# PCB_RIGID_USBC_MALE.net
KiCad netlist of a schematic drawn in EAGLE
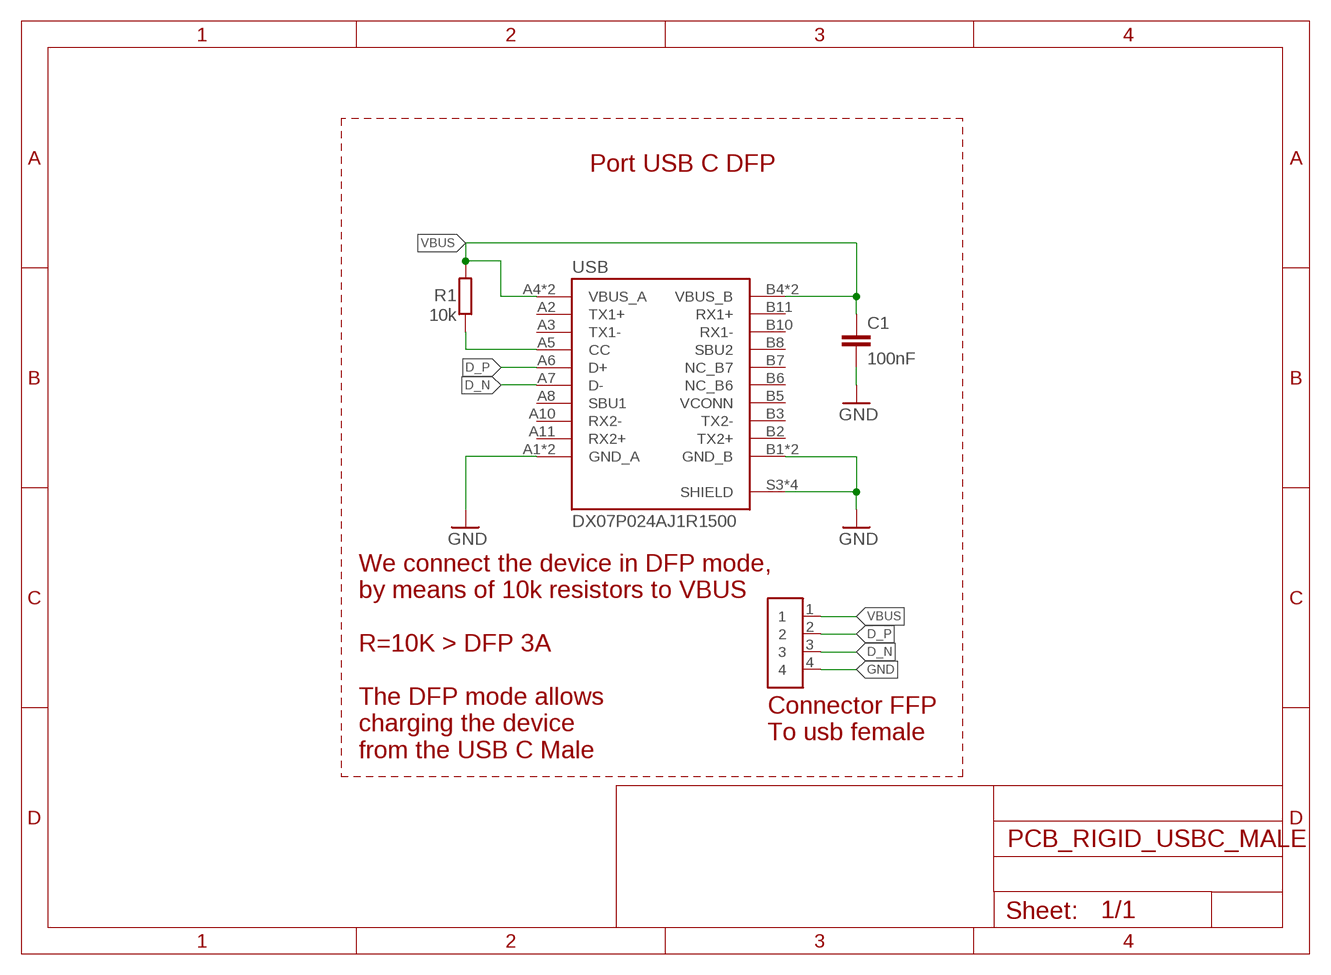
[diagram p0: schematic, sheet 1]

(export (version "E")
  (design (tool "Eeschema 10.0.6"))
  (components
    (comp (ref "C1")
      (value "100nF")
      (footprint "eagle-import:C0603")
      (libsource (lib "eagle-import") (part "C_0603"))
    )
    (comp (ref "FFP")
      (value "CONN_FLEX_2.5MM")
      (footprint "eagle-import:CONN_FLEX_2.5MM")
      (libsource (lib "eagle-import") (part "CONN_FLEX_2.5MM"))
    )
    (comp (ref "R1")
      (value "10k")
      (footprint "eagle-import:R0603")
      (libsource (lib "eagle-import") (part "R_0603"))
    )
    (comp (ref "USB")
      (value "DX07P024AJ1R1500")
      (footprint "eagle-import:JAE_DX07P024AJ1R1500")
      (fields (field (name "MF") "JAE Electronics"))
      (libsource (lib "eagle-import") (part "DX07P024AJ1R1500"))
    )
  )
  (nets
    (net (code "1") (name "D_N") (class "Default")
      (node (ref "FFP") (pin "3") (pinfunction "3_3") (pintype "bidirectional"))
      (node (ref "USB") (pin "A7") (pinfunction "D-_A7") (pintype "bidirectional"))
    )
    (net (code "2") (name "D_P") (class "Default")
      (node (ref "FFP") (pin "2") (pinfunction "2_2") (pintype "bidirectional"))
      (node (ref "USB") (pin "A6") (pinfunction "D+_A6") (pintype "bidirectional"))
    )
    (net (code "3") (name "GND") (class "Default")
      (node (ref "C1") (pin "2") (pinfunction "2_2") (pintype "passive"))
      (node (ref "FFP") (pin "4") (pinfunction "4_4") (pintype "bidirectional"))
      (node (ref "USB") (pin "A1") (pinfunction "GND_A_A1") (pintype "power_in"))
      (node (ref "USB") (pin "A12") (pinfunction "GND_A_A12") (pintype "power_in"))
      (node (ref "USB") (pin "B1") (pinfunction "GND_B_B1") (pintype "power_in"))
      (node (ref "USB") (pin "B12") (pinfunction "GND_B_B12") (pintype "power_in"))
      (node (ref "USB") (pin "S3") (pinfunction "SHIELD_S3") (pintype "passive"))
      (node (ref "USB") (pin "S4") (pinfunction "SHIELD_S4") (pintype "passive"))
      (node (ref "USB") (pin "S5") (pinfunction "SHIELD_S5") (pintype "passive"))
      (node (ref "USB") (pin "S6") (pinfunction "SHIELD_S6") (pintype "passive"))
    )
    (net (code "4") (name "Net-(USB-CC)") (class "Default")
      (node (ref "R1") (pin "1") (pinfunction "1_1") (pintype "passive"))
      (node (ref "USB") (pin "A5") (pinfunction "CC_A5") (pintype "bidirectional"))
    )
    (net (code "5") (name "VBUS") (class "Default")
      (node (ref "C1") (pin "1") (pinfunction "1_1") (pintype "passive"))
      (node (ref "FFP") (pin "1") (pinfunction "1_1") (pintype "bidirectional"))
      (node (ref "R1") (pin "2") (pinfunction "2_2") (pintype "passive"))
      (node (ref "USB") (pin "A4") (pinfunction "VBUS_A_A4") (pintype "power_in"))
      (node (ref "USB") (pin "A9") (pinfunction "VBUS_A_A9") (pintype "power_in"))
      (node (ref "USB") (pin "B4") (pinfunction "VBUS_B_B4") (pintype "power_in"))
      (node (ref "USB") (pin "B9") (pinfunction "VBUS_B_B9") (pintype "power_in"))
    )
    (net (code "6") (name "unconnected-(USB-NC_B6-PadB6)") (class "Default")
      (node (ref "USB") (pin "B6") (pinfunction "NC_B6_B6") (pintype "no_connect"))
    )
    (net (code "7") (name "unconnected-(USB-NC_B7-PadB7)") (class "Default")
      (node (ref "USB") (pin "B7") (pinfunction "NC_B7_B7") (pintype "no_connect"))
    )
    (net (code "8") (name "unconnected-(USB-RX1+-PadB11)") (class "Default")
      (node (ref "USB") (pin "B11") (pinfunction "RX1+_B11") (pintype "bidirectional"))
    )
    (net (code "9") (name "unconnected-(USB-RX1--PadB10)") (class "Default")
      (node (ref "USB") (pin "B10") (pinfunction "RX1-_B10") (pintype "bidirectional"))
    )
    (net (code "10") (name "unconnected-(USB-RX2+-PadA11)") (class "Default")
      (node (ref "USB") (pin "A11") (pinfunction "RX2+_A11") (pintype "bidirectional"))
    )
    (net (code "11") (name "unconnected-(USB-RX2--PadA10)") (class "Default")
      (node (ref "USB") (pin "A10") (pinfunction "RX2-_A10") (pintype "bidirectional"))
    )
    (net (code "12") (name "unconnected-(USB-SBU1-PadA8)") (class "Default")
      (node (ref "USB") (pin "A8") (pinfunction "SBU1_A8") (pintype "bidirectional"))
    )
    (net (code "13") (name "unconnected-(USB-SBU2-PadB8)") (class "Default")
      (node (ref "USB") (pin "B8") (pinfunction "SBU2_B8") (pintype "bidirectional"))
    )
    (net (code "14") (name "unconnected-(USB-TX1+-PadA2)") (class "Default")
      (node (ref "USB") (pin "A2") (pinfunction "TX1+_A2") (pintype "bidirectional"))
    )
    (net (code "15") (name "unconnected-(USB-TX1--PadA3)") (class "Default")
      (node (ref "USB") (pin "A3") (pinfunction "TX1-_A3") (pintype "bidirectional"))
    )
    (net (code "16") (name "unconnected-(USB-TX2+-PadB2)") (class "Default")
      (node (ref "USB") (pin "B2") (pinfunction "TX2+_B2") (pintype "bidirectional"))
    )
    (net (code "17") (name "unconnected-(USB-TX2--PadB3)") (class "Default")
      (node (ref "USB") (pin "B3") (pinfunction "TX2-_B3") (pintype "bidirectional"))
    )
    (net (code "18") (name "unconnected-(USB-VCONN-PadB5)") (class "Default")
      (node (ref "USB") (pin "B5") (pinfunction "VCONN_B5") (pintype "bidirectional"))
    )
  )
)
